# LightLink.net
KiCad netlist of a schematic drawn in Altium Designer
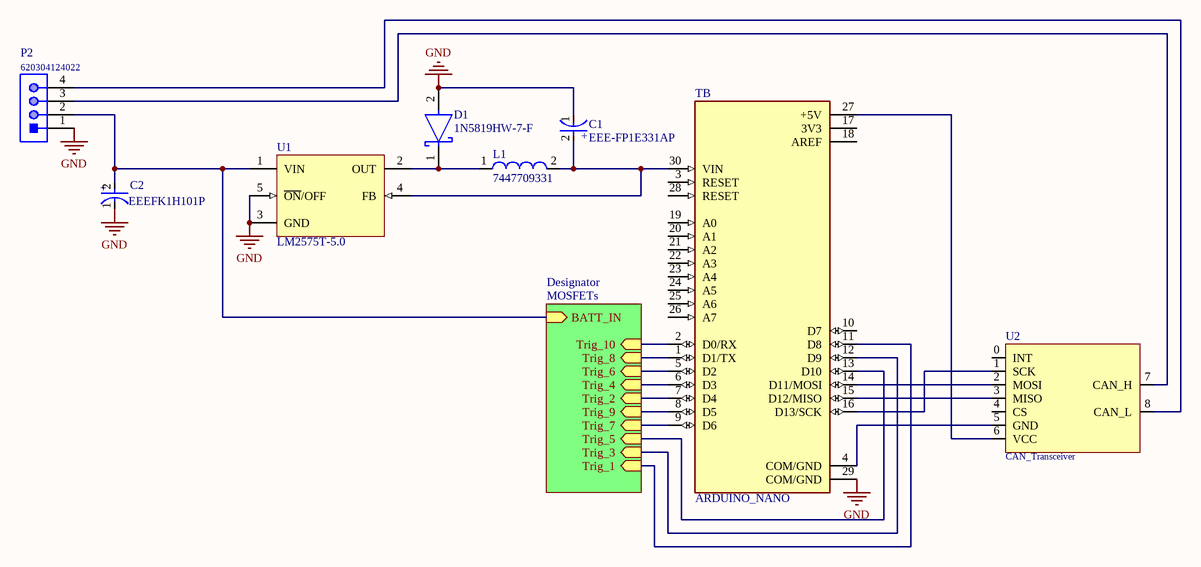
[diagram p0: LightLink.SchDoc]

(export (version "E")
  (design (tool "Eeschema 10.0.6"))
  (components
    (comp (ref "C1")
      (value "EEE-FP1E331AP")
      (footprint "FP-FPF-MFG")
      (description "CAP ALUM 330UF 20% 25V SMD")
      (fields (field (name "VOLTAGE") "25V") (field (name "TOLERANCE") "20%"))
      (libsource (lib "Altium Content Vault") (part "203bc49f2ac43e59fd269a8c329ed05"))
    )
    (comp (ref "C2")
      (value "EEEFK1H101P")
      (footprint "FP-FKF-MFG")
      (description "CAP ALUM 100UF 20% 50V SMD")
      (fields (field (name "VOLTAGE") "50V") (field (name "TOLERANCE") "20%"))
      (libsource (lib "Altium Content Vault") (part "a00bbbee19879c290e62620ae7e47b1"))
    )
    (comp (ref "D1")
      (value "1N5819HW-7-F")
      (footprint "FP-SOD123-IPC_A")
      (description "DIODE SCHOTTKY 40V 1A SOD123")
      (libsource (lib "Altium Content Vault") (part "1d6ec82d83fb6aee721767c19dac4b9"))
    )
    (comp (ref "L1")
      (value "7447709331")
      (footprint "WE-PD-XXL")
      (description "SMD-Shielded Power Inductor WE-PD, L = 330 µH")
      (libsource (lib "Altium Content Vault") (part "PAS-IND-INDUCTOR-2"))
    )
    (comp (ref "P2")
      (value "620304124022")
      (footprint "620304124022")
      (description "Male Shrouded Header WR-WTB, SMT, Vertical, pitch 2 mm, 1 x 4 position")
      (fields (field (name "MANUFACTURER") "Wurth Elektronik") (field (name "PUBLISHER") "WurthElektronik"))
      (libsource (lib "Altium Content Vault") (part "WE-CN-1P-M-R4"))
    )
    (comp (ref "TB")
      (value "ARDUINO_NANO")
      (footprint "SHIELD_ARDUINO_NANO")
      (description "ATSAMD21G18A Arduino Nano 33 IoT SAM D ARMÂ® CortexÂ®-M0+ MCU 32-Bit Embedded Evaluation Board")
      (fields (field (name "MF") "Arduino") (field (name "MP") "ARDUINO NANO"))
      (libsource (lib "uORocketry Hardware") (part "ARDUINO_NANO"))
    )
    (comp (ref "U1")
      (value "LM2575T-5.0")
      (footprint "KC0005A")
      (description "SIMPLE SWITCHER® 1A Step-Down Voltage Regulator, 5-pin TO-220")
      (fields (field (name "MANUFACTURER") "Texas Instruments"))
      (libsource (lib "Altium Content Vault") (part "PM-REG-LM2575HVT-12"))
    )
    (comp (ref "U2")
      (value "CAN_Transceiver")
      (description "Footprint for existing SPI transceiver")
      (libsource (lib "lightLinkSchLib") (part "CAN_Transceiver"))
    )
  )
  (nets
    (net (code "1") (name "/BATT_IN") (class "Default")
      (node (ref "C2") (pin "2") (pinfunction "A_2") (pintype "passive"))
      (node (ref "P2") (pin "2") (pinfunction "2_2") (pintype "passive"))
      (node (ref "U1") (pin "1") (pinfunction "VIN_1") (pintype "power_in"))
    )
    (net (code "2") (name "/Trig_1") (class "Default")
      (node (ref "TB") (pin "11") (pinfunction "D8_11") (pintype "bidirectional"))
    )
    (net (code "3") (name "/Trig_2") (class "Default")
      (node (ref "TB") (pin "7") (pinfunction "D4_7") (pintype "bidirectional"))
    )
    (net (code "4") (name "/Trig_3") (class "Default")
      (node (ref "TB") (pin "12") (pinfunction "D9_12") (pintype "bidirectional"))
    )
    (net (code "5") (name "/Trig_4") (class "Default")
      (node (ref "TB") (pin "6") (pinfunction "D3_6") (pintype "bidirectional"))
    )
    (net (code "6") (name "/Trig_5") (class "Default")
      (node (ref "TB") (pin "13") (pinfunction "D10_13") (pintype "bidirectional"))
    )
    (net (code "7") (name "/Trig_6") (class "Default")
      (node (ref "TB") (pin "5") (pinfunction "D2_5") (pintype "bidirectional"))
    )
    (net (code "8") (name "/Trig_7") (class "Default")
      (node (ref "TB") (pin "9") (pinfunction "D6_9") (pintype "bidirectional"))
    )
    (net (code "9") (name "/Trig_8") (class "Default")
      (node (ref "TB") (pin "1") (pinfunction "D1/TX_1") (pintype "bidirectional"))
    )
    (net (code "10") (name "/Trig_9") (class "Default")
      (node (ref "TB") (pin "8") (pinfunction "D5_8") (pintype "bidirectional"))
    )
    (net (code "11") (name "/Trig_10") (class "Default")
      (node (ref "TB") (pin "2") (pinfunction "D0/RX_2") (pintype "bidirectional"))
    )
    (net (code "12") (name "GND") (class "Default")
      (node (ref "C1") (pin "1") (pinfunction "C_1") (pintype "passive"))
      (node (ref "C2") (pin "1") (pinfunction "C_1") (pintype "passive"))
      (node (ref "D1") (pin "2") (pinfunction "A_2") (pintype "passive"))
      (node (ref "P2") (pin "1") (pinfunction "1_1") (pintype "passive"))
      (node (ref "TB") (pin "29") (pinfunction "COM/GND_29") (pintype "power_in"))
      (node (ref "U1") (pin "3") (pinfunction "GND_3") (pintype "power_in"))
      (node (ref "U1") (pin "5") (pinfunction "~{ON}/OFF_5") (pintype "input"))
    )
    (net (code "13") (name "Net-(C1-A)") (class "Default")
      (node (ref "C1") (pin "2") (pinfunction "A_2") (pintype "passive"))
      (node (ref "L1") (pin "2") (pinfunction "2_2") (pintype "passive"))
      (node (ref "TB") (pin "30") (pinfunction "VIN_30") (pintype "input"))
      (node (ref "U1") (pin "4") (pinfunction "FB_4") (pintype "input"))
    )
    (net (code "14") (name "Net-(D1-C)") (class "Default")
      (node (ref "D1") (pin "1") (pinfunction "C_1") (pintype "passive"))
      (node (ref "L1") (pin "1") (pinfunction "1_1") (pintype "passive"))
      (node (ref "U1") (pin "2") (pinfunction "OUT_2") (pintype "power_in"))
    )
    (net (code "15") (name "Net-(TB-+5V)") (class "Default")
      (node (ref "TB") (pin "27") (pinfunction "+5V_27") (pintype "power_in"))
      (node (ref "U2") (pin "6") (pinfunction "VCC_6") (pintype "passive"))
    )
    (net (code "16") (name "Net-(TB-D11{slash}MOSI)") (class "Default")
      (node (ref "TB") (pin "14") (pinfunction "D11/MOSI_14") (pintype "bidirectional"))
      (node (ref "U2") (pin "2") (pinfunction "MOSI_2") (pintype "passive"))
    )
    (net (code "17") (name "Net-(TB-D12{slash}MISO)") (class "Default")
      (node (ref "TB") (pin "15") (pinfunction "D12/MISO_15") (pintype "bidirectional"))
      (node (ref "U2") (pin "3") (pinfunction "MISO_3") (pintype "passive"))
    )
    (net (code "18") (name "Net-(TB-D13{slash}SCK)") (class "Default")
      (node (ref "TB") (pin "16") (pinfunction "D13/SCK_16") (pintype "bidirectional"))
      (node (ref "U2") (pin "1") (pinfunction "SCK_1") (pintype "passive"))
    )
    (net (code "19") (name "Net-(U2-CAN_H)") (class "Default")
      (node (ref "P2") (pin "3") (pinfunction "3_3") (pintype "passive"))
      (node (ref "U2") (pin "7") (pinfunction "CAN_H_7") (pintype "passive"))
    )
    (net (code "20") (name "Net-(U2-CAN_L)") (class "Default")
      (node (ref "P2") (pin "4") (pinfunction "4_4") (pintype "passive"))
      (node (ref "U2") (pin "8") (pinfunction "CAN_L_8") (pintype "passive"))
    )
    (net (code "21") (name "Net-(U2-GND)") (class "Default")
      (node (ref "TB") (pin "4") (pinfunction "COM/GND_4") (pintype "power_in"))
      (node (ref "U2") (pin "5") (pinfunction "GND_5") (pintype "passive"))
    )
    (net (code "22") (name "unconnected-(TB-3V3-Pad17)") (class "Default")
      (node (ref "TB") (pin "17") (pinfunction "3V3_17") (pintype "power_in"))
    )
    (net (code "23") (name "unconnected-(TB-A0-Pad19)") (class "Default")
      (node (ref "TB") (pin "19") (pinfunction "A0_19") (pintype "input"))
    )
    (net (code "24") (name "unconnected-(TB-A1-Pad20)") (class "Default")
      (node (ref "TB") (pin "20") (pinfunction "A1_20") (pintype "input"))
    )
    (net (code "25") (name "unconnected-(TB-A2-Pad21)") (class "Default")
      (node (ref "TB") (pin "21") (pinfunction "A2_21") (pintype "input"))
    )
    (net (code "26") (name "unconnected-(TB-A3-Pad22)") (class "Default")
      (node (ref "TB") (pin "22") (pinfunction "A3_22") (pintype "input"))
    )
    (net (code "27") (name "unconnected-(TB-A4-Pad23)") (class "Default")
      (node (ref "TB") (pin "23") (pinfunction "A4_23") (pintype "input"))
    )
    (net (code "28") (name "unconnected-(TB-A5-Pad24)") (class "Default")
      (node (ref "TB") (pin "24") (pinfunction "A5_24") (pintype "input"))
    )
    (net (code "29") (name "unconnected-(TB-A6-Pad25)") (class "Default")
      (node (ref "TB") (pin "25") (pinfunction "A6_25") (pintype "input"))
    )
    (net (code "30") (name "unconnected-(TB-A7-Pad26)") (class "Default")
      (node (ref "TB") (pin "26") (pinfunction "A7_26") (pintype "input"))
    )
    (net (code "31") (name "unconnected-(TB-AREF-Pad18)") (class "Default")
      (node (ref "TB") (pin "18") (pinfunction "AREF_18") (pintype "power_in"))
    )
    (net (code "32") (name "unconnected-(TB-D7-Pad10)") (class "Default")
      (node (ref "TB") (pin "10") (pinfunction "D7_10") (pintype "bidirectional"))
    )
    (net (code "33") (name "unconnected-(TB-RESET-Pad3)") (class "Default")
      (node (ref "TB") (pin "3") (pinfunction "RESET_3") (pintype "input"))
    )
    (net (code "34") (name "unconnected-(TB-RESET-Pad28)") (class "Default")
      (node (ref "TB") (pin "28") (pinfunction "RESET_28") (pintype "input"))
    )
    (net (code "35") (name "unconnected-(U2-CS-Pad4)") (class "Default")
      (node (ref "U2") (pin "4") (pinfunction "CS_4") (pintype "passive"))
    )
    (net (code "36") (name "unconnected-(U2-INT-Pad0)") (class "Default")
      (node (ref "U2") (pin "0") (pinfunction "INT_0") (pintype "passive"))
    )
  )
)
